# FPGA_PART2.net
KiCad netlist of a schematic drawn in Altium Designer
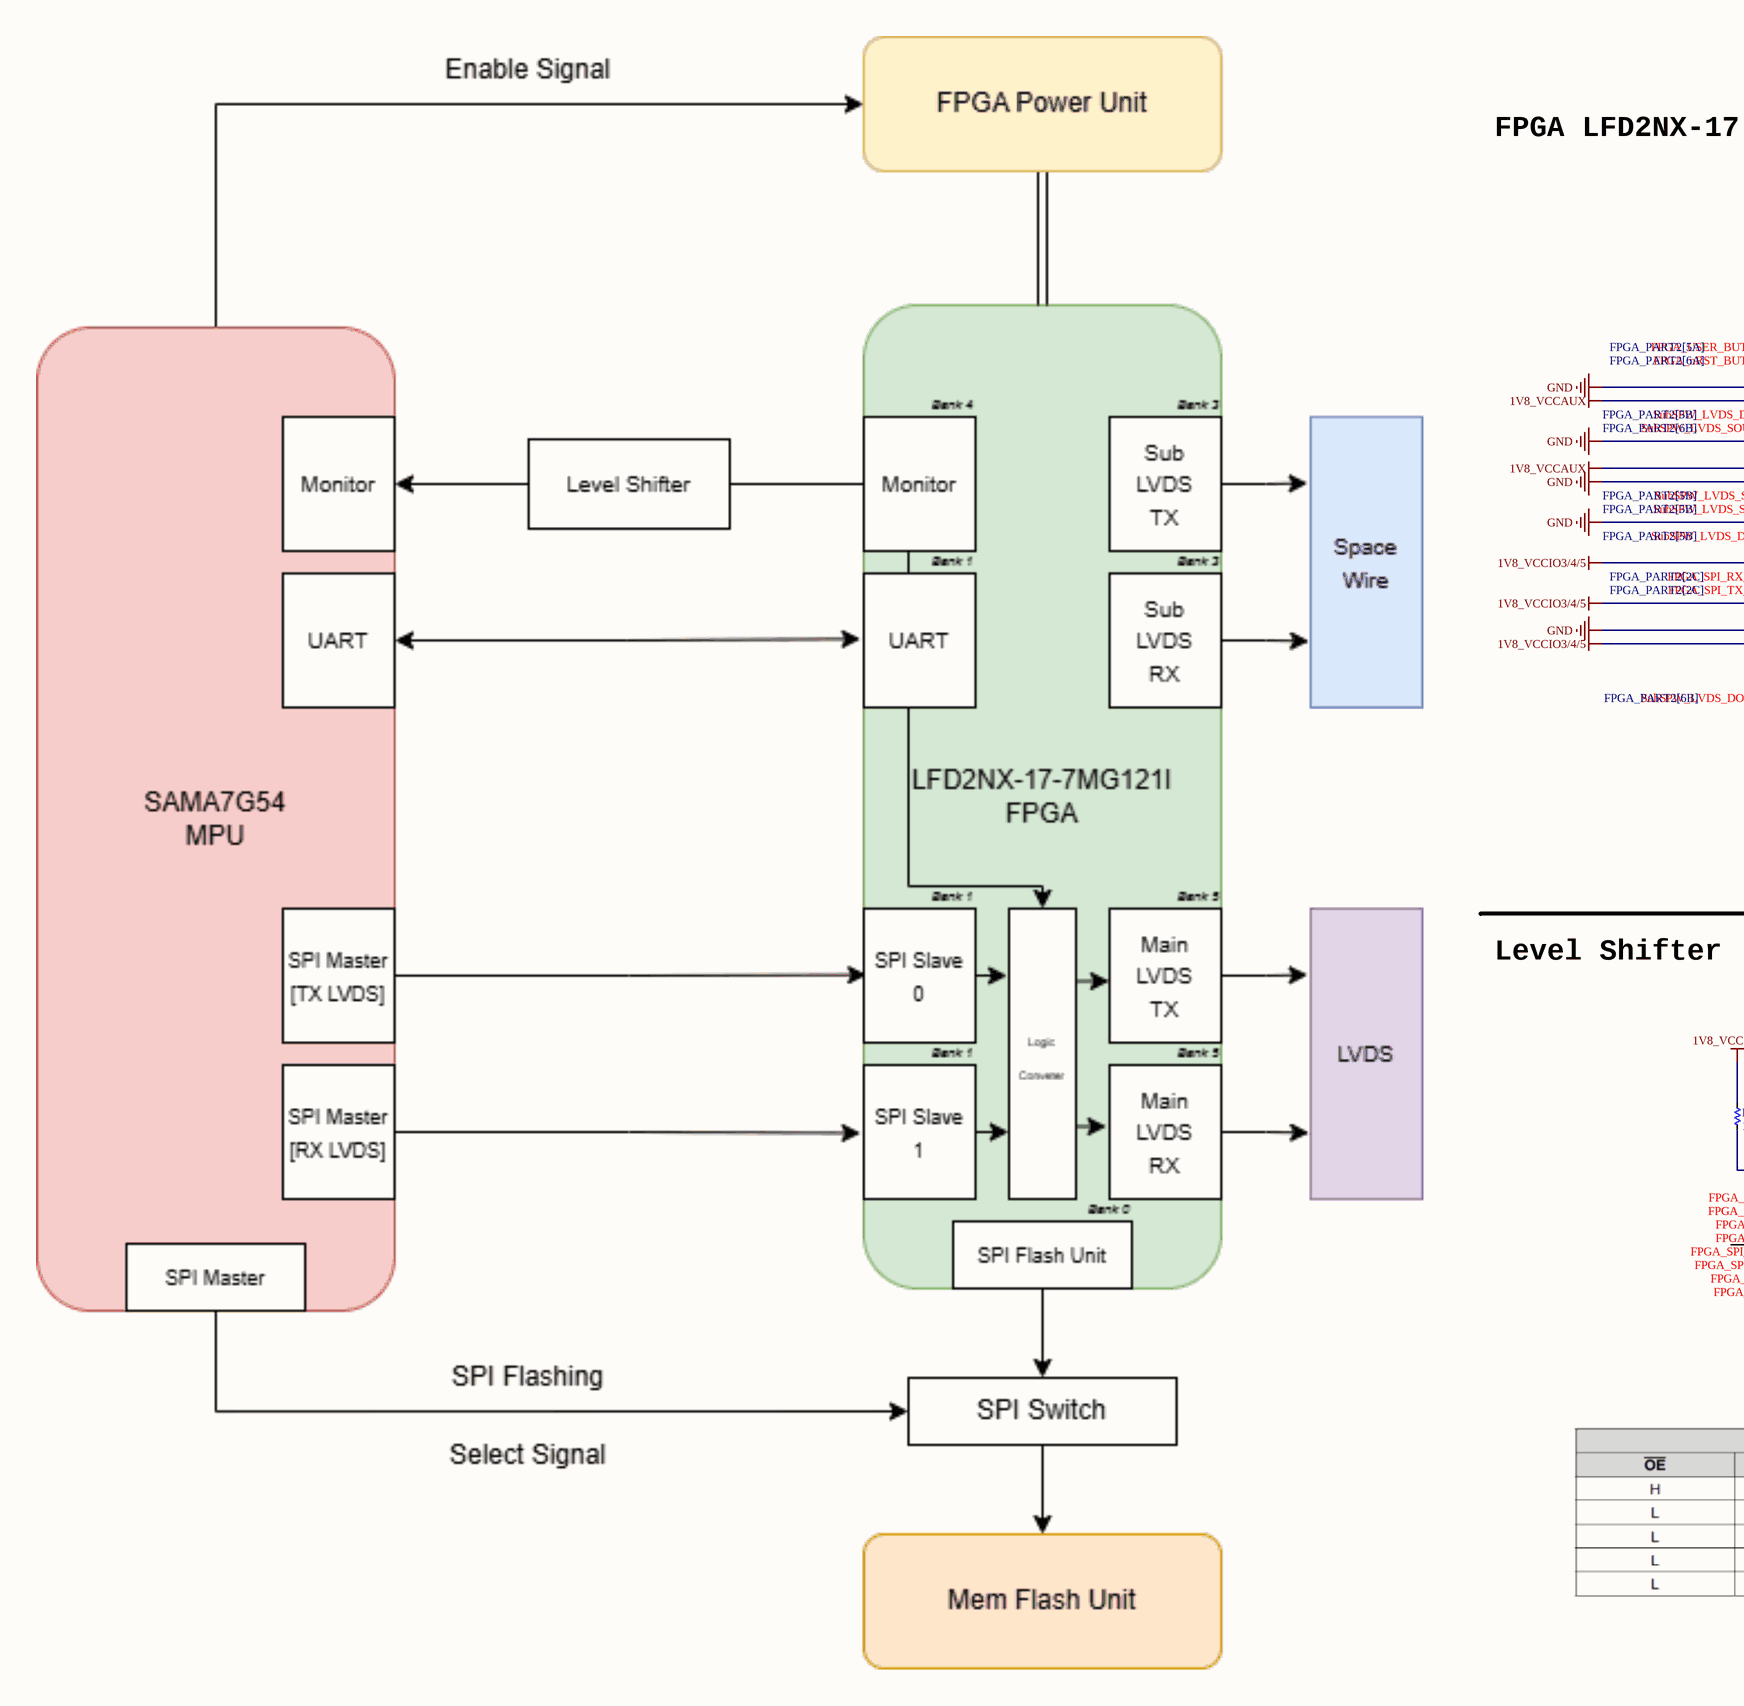
[diagram p0: FPGA_PART2.SchDoc, left]
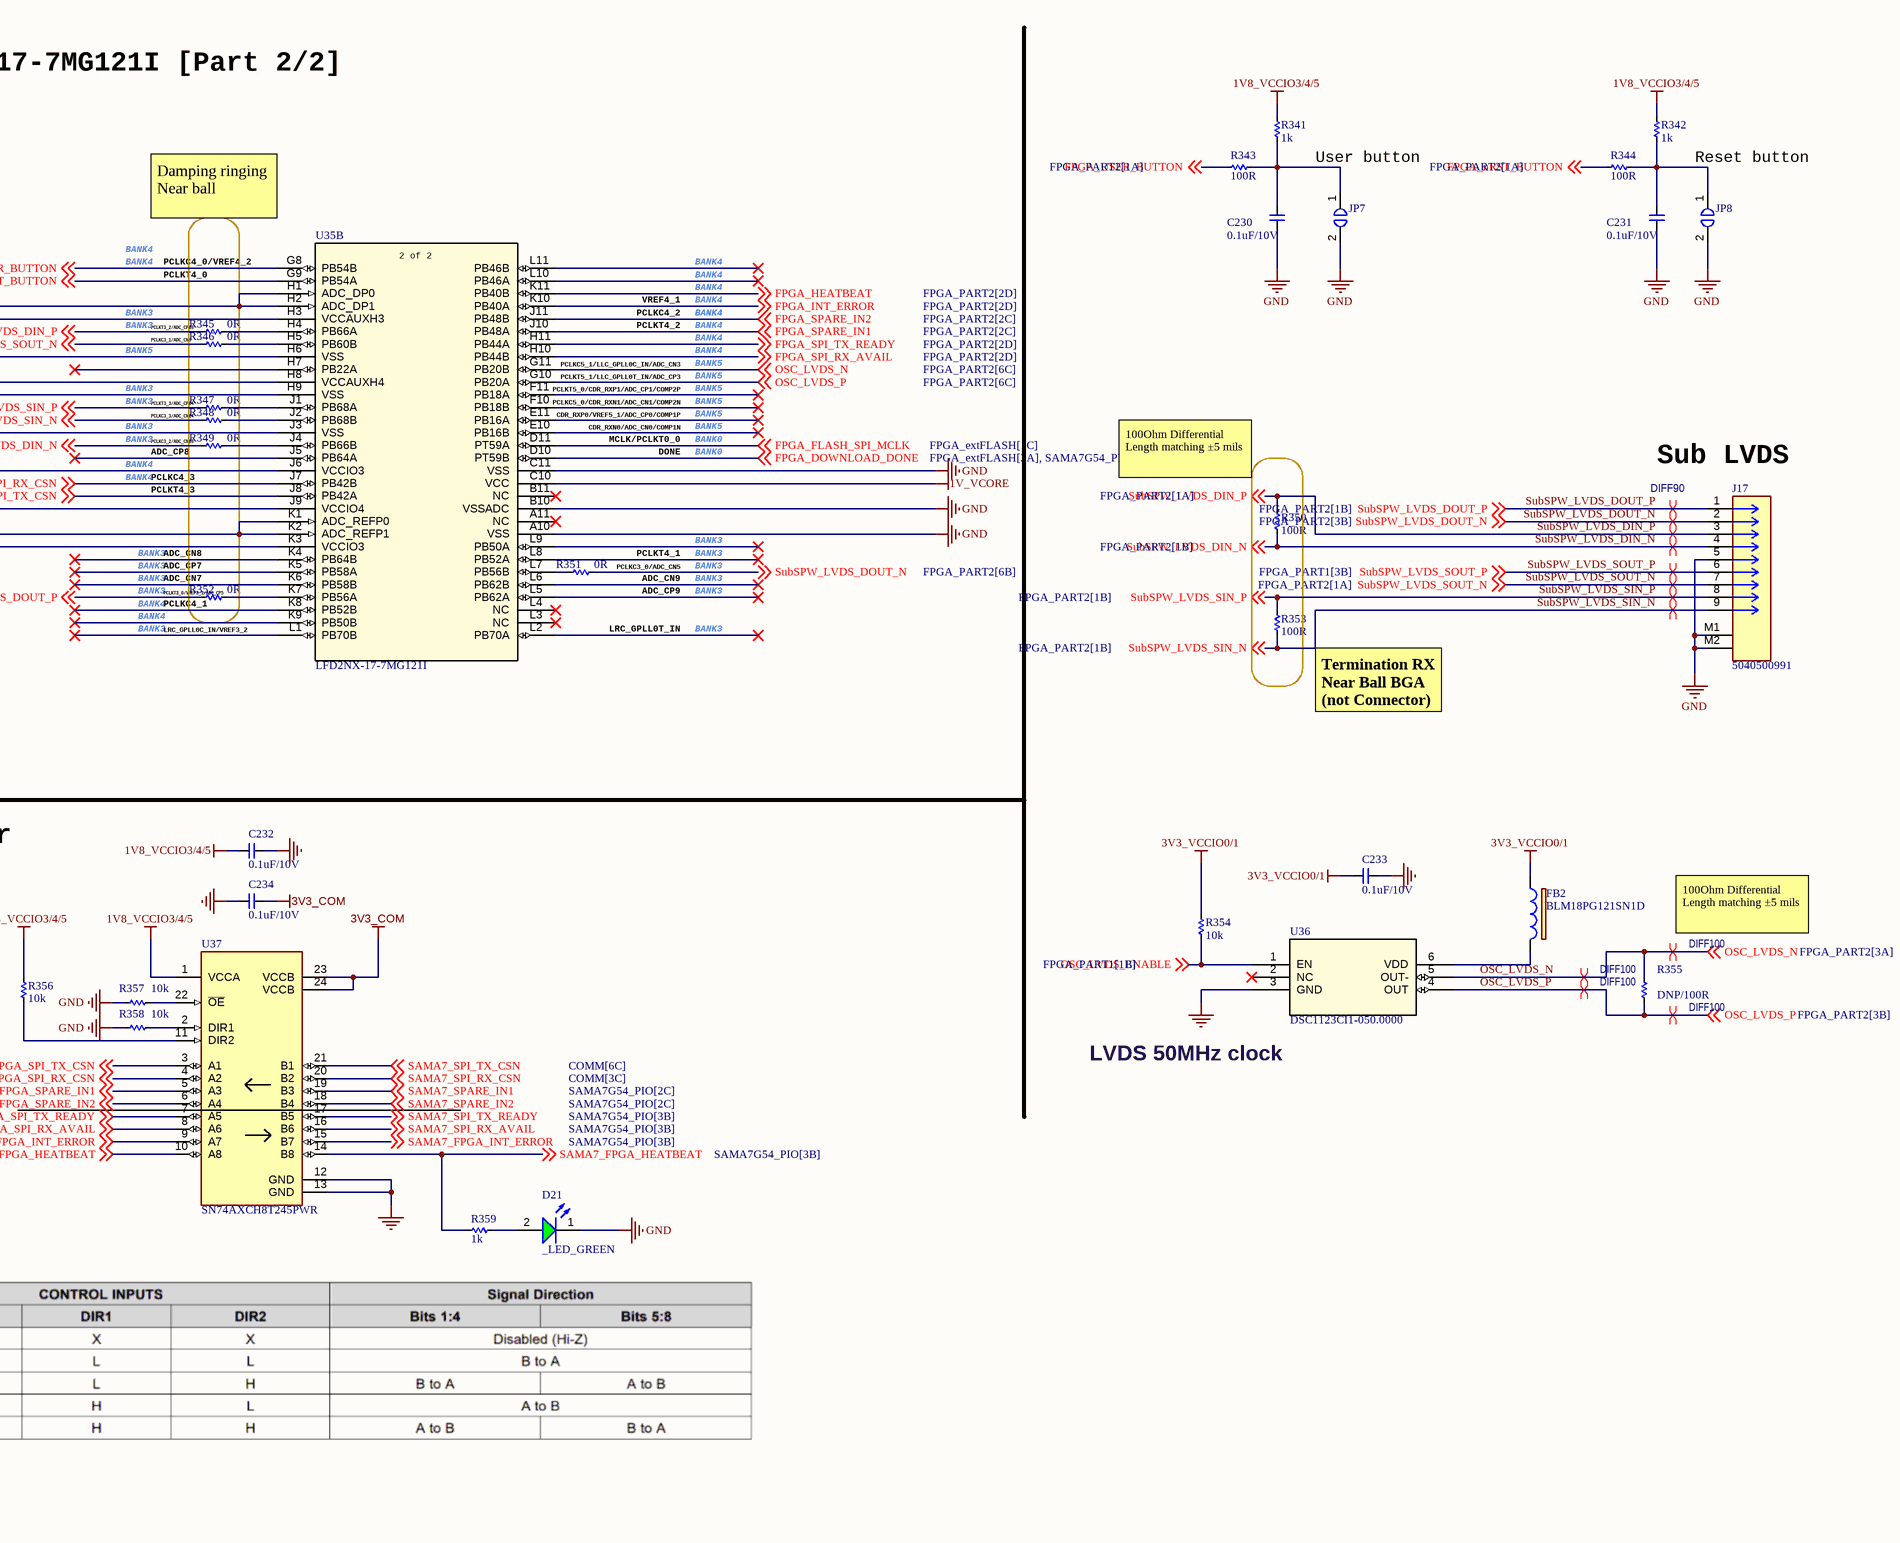
[diagram p1: FPGA_PART2.SchDoc, right]

(export (version "E")
  (design (tool "Eeschema 10.0.6"))
  (components
    (comp (ref "C230")
      (value "0.1uF/10V")
      (footprint "CAP_C_1005X50_L")
      (description "CAP")
      (libsource (lib "LABLIB") (part "_CAP_C_2"))
    )
    (comp (ref "C231")
      (value "0.1uF/10V")
      (footprint "CAP_C_1005X50_L")
      (description "CAP")
      (libsource (lib "LABLIB") (part "_CAP_C_2"))
    )
    (comp (ref "C232")
      (value "0.1uF/10V")
      (footprint "CAP_C_1005X50_L")
      (description "CAP")
      (libsource (lib "LABLIB") (part "_CAP_C_2"))
    )
    (comp (ref "C233")
      (value "0.1uF/10V")
      (footprint "CAP_C_1005X50_L")
      (description "CAP")
      (libsource (lib "LABLIB") (part "_CAP_C_2"))
    )
    (comp (ref "C234")
      (value "0.1uF/10V")
      (footprint "CAP_C_1005X50_L")
      (description "CAP")
      (libsource (lib "LABLIB") (part "_CAP_C_2"))
    )
    (comp (ref "D21")
      (value "_LED_GREEN")
      (footprint "LED_0603")
      (description "LED GREEN CLEAR 0603 SMD")
      (libsource (lib "IFBschelib") (part "LED_GREEN"))
    )
    (comp (ref "FB2")
      (value "BLM18PG121SN1D")
      (footprint "IND_C_1608X60")
      (description "FERRITE BEAD 120 OHM 0603 1LN")
      (fields (field (name "COPYRIGHT") "Copyright (C) 2025 Ultra Librarian. All rights reserved."))
      (libsource (lib "IFBschelib") (part "BLM18PG121SN1D"))
    )
    (comp (ref "J17")
      (value "5040500991")
      (footprint "MOLEX_5040500991")
      (description "Connector Header Surface Mount, Right Angle 9 position 0.059\" (1.50mm)")
      (libsource (lib "IFBschelib") (part "5040500991"))
    )
    (comp (ref "JP7") (value "~") (footprint "JUMPER_1608") (libsource (lib "LABLIB") (part "JUMPER_1_1")))
    (comp (ref "JP8") (value "~") (footprint "JUMPER_1608") (libsource (lib "LABLIB") (part "JUMPER_1_1")))
    (comp (ref "R341")
      (value "1k")
      (footprint "RES_C_1005x30_L")
      (description "RES")
      (libsource (lib "LABLIB") (part "_RES_B_2"))
    )
    (comp (ref "R342")
      (value "1k")
      (footprint "RES_C_1005x30_L")
      (description "RES")
      (libsource (lib "LABLIB") (part "_RES_B_2"))
    )
    (comp (ref "R343")
      (value "100R")
      (footprint "RES_C_1005x30_L")
      (description "RES")
      (libsource (lib "LABLIB") (part "_RES_B_2"))
    )
    (comp (ref "R344")
      (value "100R")
      (footprint "RES_C_1005x30_L")
      (description "RES")
      (libsource (lib "LABLIB") (part "_RES_B_2"))
    )
    (comp (ref "R345")
      (value "0R")
      (footprint "RES_C_1005x30_L")
      (description "RES")
      (libsource (lib "LABLIB") (part "_RES_B_2"))
    )
    (comp (ref "R346")
      (value "0R")
      (footprint "RES_C_1005x30_L")
      (description "RES")
      (libsource (lib "LABLIB") (part "_RES_B_2"))
    )
    (comp (ref "R347")
      (value "0R")
      (footprint "RES_C_1005x30_L")
      (description "RES")
      (libsource (lib "LABLIB") (part "_RES_B_2"))
    )
    (comp (ref "R348")
      (value "0R")
      (footprint "RES_C_1005x30_L")
      (description "RES")
      (libsource (lib "LABLIB") (part "_RES_B_2"))
    )
    (comp (ref "R349")
      (value "0R")
      (footprint "RES_C_1005x30_L")
      (description "RES")
      (libsource (lib "LABLIB") (part "_RES_B_2"))
    )
    (comp (ref "R350")
      (value "100R")
      (footprint "RES_C_1005x30_L")
      (description "RES")
      (libsource (lib "LABLIB") (part "_RES_B_2"))
    )
    (comp (ref "R351")
      (value "0R")
      (footprint "RES_C_1005x30_L")
      (description "RES")
      (libsource (lib "LABLIB") (part "_RES_B_2"))
    )
    (comp (ref "R352")
      (value "0R")
      (footprint "RES_C_1005x30_L")
      (description "RES")
      (libsource (lib "LABLIB") (part "_RES_B_2"))
    )
    (comp (ref "R353")
      (value "100R")
      (footprint "RES_C_1005x30_L")
      (description "RES")
      (libsource (lib "LABLIB") (part "_RES_B_2"))
    )
    (comp (ref "R354")
      (value "10k")
      (footprint "RES_C_1005x30_L")
      (description "RES")
      (libsource (lib "LABLIB") (part "_RES_B_2"))
    )
    (comp (ref "R355")
      (value "DNP/100R")
      (footprint "RES_C_1005x30_L")
      (description "RES")
      (libsource (lib "IFBschelib") (part "_RES_B_2"))
    )
    (comp (ref "R356")
      (value "10k")
      (footprint "RES_C_1005x30_L")
      (description "RES")
      (libsource (lib "LABLIB") (part "_RES_B_2"))
    )
    (comp (ref "R357")
      (value "10k")
      (footprint "RES_C_1005x30_L")
      (description "RES")
      (libsource (lib "LABLIB") (part "_RES_B_2"))
    )
    (comp (ref "R358")
      (value "10k")
      (footprint "RES_C_1005x30_L")
      (description "RES")
      (libsource (lib "LABLIB") (part "_RES_B_2"))
    )
    (comp (ref "R359")
      (value "1k")
      (footprint "RES_C_1005x30_L")
      (description "RES")
      (libsource (lib "LABLIB") (part "_RES_B_2"))
    )
    (comp (ref "U35")
      (value "LFD2NX-17-7MG121I")
      (footprint "csfBGA121_LAT")
      (description "Description")
      (fields (field (name "COPYRIGHT") "Copyright (C) 2025 Ultra Librarian. All rights reserved."))
      (libsource (lib "IFBschelib_offline") (part "LFD2NX-17-7MG121I"))
    )
    (comp (ref "U36")
      (value "DSC1123CI1-050.0000")
      (footprint "VDFN6_3P2X2P5_MCH")
      (description "No Description Available")
      (fields
        (field (name "MANUFACTURER_PART_NUMBER") "DSC1103CI2-180.0000T")
        (field (name "COPYRIGHT") "Copyright (C) 2026 Ultra Librarian. All rights reserved.")
      )
      (libsource (lib "IFBschelib") (part "DSC11x3CIx-x"))
    )
    (comp (ref "U37")
      (value "SN74AXCH8T245PWR")
      (footprint "SOP65P640X120-24N")
      (description "8-Bit Dual-Supply Bus Transceiver")
      (fields (field (name "MF") "Texas Instruments"))
      (libsource (lib "LABLIB") (part "IC_voltage_level_SN74AXCH8T245PWR"))
    )
  )
  (nets
    (net (code "1") (name "1V8_VCCAUX") (class "Default")
      (node (ref "U35") (pin "H3") (pinfunction "VCCAUXH3_H3") (pintype "power_in"))
      (node (ref "U35") (pin "H8") (pinfunction "VCCAUXH4_H8") (pintype "power_in"))
    )
    (net (code "2") (name "1V8_VCCIO3{slash}4{slash}5") (class "Default")
      (node (ref "C232") (pin "2") (pinfunction "2_2") (pintype "passive"))
      (node (ref "R341") (pin "2") (pinfunction "2_2") (pintype "passive"))
      (node (ref "R342") (pin "2") (pinfunction "2_2") (pintype "passive"))
      (node (ref "R356") (pin "2") (pinfunction "2_2") (pintype "passive"))
      (node (ref "U35") (pin "J6") (pinfunction "VCCIO3_J6") (pintype "power_in"))
      (node (ref "U35") (pin "J9") (pinfunction "VCCIO4_J9") (pintype "power_in"))
      (node (ref "U35") (pin "K3") (pinfunction "VCCIO3_K3") (pintype "power_in"))
      (node (ref "U37") (pin "1") (pinfunction "VCCA_1") (pintype "power_in"))
    )
    (net (code "3") (name "1V_VCORE") (class "Default")
      (node (ref "U35") (pin "C10") (pinfunction "VCC_C10") (pintype "power_in"))
    )
    (net (code "4") (name "3V3_COM") (class "Default")
      (node (ref "C234") (pin "2") (pinfunction "2_2") (pintype "passive"))
      (node (ref "U37") (pin "23") (pinfunction "VCCB_23") (pintype "power_in"))
      (node (ref "U37") (pin "24") (pinfunction "VCCB_24") (pintype "power_in"))
    )
    (net (code "5") (name "3V3_VCCIO0{slash}1") (class "Default")
      (node (ref "C233") (pin "2") (pinfunction "2_2") (pintype "passive"))
      (node (ref "FB2") (pin "2") (pinfunction "2_2") (pintype "passive"))
      (node (ref "R354") (pin "2") (pinfunction "2_2") (pintype "passive"))
    )
    (net (code "6") (name "FPGA_DOWNLOAD_DONE") (class "Default")
      (node (ref "U35") (pin "D10") (pinfunction "PT59B_D10") (pintype "bidirectional"))
    )
    (net (code "7") (name "FPGA_FLASH_SPI_MCLK") (class "Default")
      (node (ref "U35") (pin "D11") (pinfunction "PT59A_D11") (pintype "bidirectional"))
    )
    (net (code "8") (name "FPGA_HEATBEAT") (class "Default")
      (node (ref "U35") (pin "K11") (pinfunction "PB40B_K11") (pintype "bidirectional"))
      (node (ref "U37") (pin "10") (pinfunction "A8_10") (pintype "bidirectional"))
    )
    (net (code "9") (name "FPGA_INT_ERROR") (class "Default")
      (node (ref "U35") (pin "K10") (pinfunction "PB40A_K10") (pintype "bidirectional"))
      (node (ref "U37") (pin "9") (pinfunction "A7_9") (pintype "bidirectional"))
    )
    (net (code "10") (name "FPGA_SPARE_IN1") (class "Default")
      (node (ref "U35") (pin "J10") (pinfunction "PB48A_J10") (pintype "bidirectional"))
      (node (ref "U37") (pin "5") (pinfunction "A3_5") (pintype "bidirectional"))
    )
    (net (code "11") (name "FPGA_SPARE_IN2") (class "Default")
      (node (ref "U35") (pin "J11") (pinfunction "PB48B_J11") (pintype "bidirectional"))
      (node (ref "U37") (pin "6") (pinfunction "A4_6") (pintype "bidirectional"))
    )
    (net (code "12") (name "FPGA_SPI_RX_AVAIL") (class "Default")
      (node (ref "U35") (pin "H10") (pinfunction "PB44B_H10") (pintype "bidirectional"))
      (node (ref "U37") (pin "8") (pinfunction "A6_8") (pintype "bidirectional"))
    )
    (net (code "13") (name "FPGA_SPI_RX_CSN") (class "Default")
      (node (ref "U35") (pin "J7") (pinfunction "PB42B_J7") (pintype "bidirectional"))
      (node (ref "U37") (pin "4") (pinfunction "A2_4") (pintype "bidirectional"))
    )
    (net (code "14") (name "FPGA_SPI_TX_CSN") (class "Default")
      (node (ref "U35") (pin "J8") (pinfunction "PB42A_J8") (pintype "bidirectional"))
      (node (ref "U37") (pin "3") (pinfunction "A1_3") (pintype "bidirectional"))
    )
    (net (code "15") (name "FPGA_SPI_TX_READY") (class "Default")
      (node (ref "U35") (pin "H11") (pinfunction "PB44A_H11") (pintype "bidirectional"))
      (node (ref "U37") (pin "7") (pinfunction "A5_7") (pintype "bidirectional"))
    )
    (net (code "16") (name "FPGA_USER_BUTTON") (class "Default")
      (node (ref "R343") (pin "1") (pinfunction "1_1") (pintype "passive"))
      (node (ref "U35") (pin "G8") (pinfunction "PB54B_G8") (pintype "bidirectional"))
    )
    (net (code "17") (name "FPGA_nRST_BUTTON") (class "Default")
      (node (ref "R344") (pin "1") (pinfunction "1_1") (pintype "passive"))
      (node (ref "U35") (pin "G9") (pinfunction "PB54A_G9") (pintype "bidirectional"))
    )
    (net (code "18") (name "GND") (class "Default")
      (node (ref "C230") (pin "1") (pinfunction "1_1") (pintype "passive"))
      (node (ref "C231") (pin "1") (pinfunction "1_1") (pintype "passive"))
      (node (ref "C232") (pin "1") (pinfunction "1_1") (pintype "passive"))
      (node (ref "C233") (pin "1") (pinfunction "1_1") (pintype "passive"))
      (node (ref "C234") (pin "1") (pinfunction "1_1") (pintype "passive"))
      (node (ref "D21") (pin "1") (pinfunction "K_1") (pintype "passive"))
      (node (ref "J17") (pin "5") (pinfunction "5_5") (pintype "passive"))
      (node (ref "J17") (pin "M1") (pinfunction "M1_M1") (pintype "passive"))
      (node (ref "J17") (pin "M2") (pinfunction "M2_M2") (pintype "passive"))
      (node (ref "JP7") (pin "2") (pinfunction "2_2") (pintype "passive"))
      (node (ref "JP8") (pin "2") (pinfunction "2_2") (pintype "passive"))
      (node (ref "R357") (pin "1") (pinfunction "1_1") (pintype "passive"))
      (node (ref "R358") (pin "1") (pinfunction "1_1") (pintype "passive"))
      (node (ref "U35") (pin "A10") (pinfunction "VSS_A10") (pintype "power_in"))
      (node (ref "U35") (pin "B10") (pinfunction "VSSADC_B10") (pintype "power_in"))
      (node (ref "U35") (pin "C11") (pinfunction "VSS_C11") (pintype "power_in"))
      (node (ref "U35") (pin "H1") (pinfunction "ADC_DP0_H1") (pintype "input"))
      (node (ref "U35") (pin "H2") (pinfunction "ADC_DP1_H2") (pintype "input"))
      (node (ref "U35") (pin "H6") (pinfunction "VSS_H6") (pintype "power_in"))
      (node (ref "U35") (pin "H9") (pinfunction "VSS_H9") (pintype "power_in"))
      (node (ref "U35") (pin "J3") (pinfunction "VSS_J3") (pintype "power_in"))
      (node (ref "U35") (pin "K1") (pinfunction "ADC_REFP0_K1") (pintype "input"))
      (node (ref "U35") (pin "K2") (pinfunction "ADC_REFP1_K2") (pintype "input"))
      (node (ref "U36") (pin "3") (pinfunction "GND_3") (pintype "power_in"))
      (node (ref "U37") (pin "12") (pinfunction "GND_12") (pintype "power_in"))
      (node (ref "U37") (pin "13") (pinfunction "GND_13") (pintype "power_in"))
    )
    (net (code "19") (name "Net-(C230-Pad2)") (class "Default")
      (node (ref "C230") (pin "2") (pinfunction "2_2") (pintype "passive"))
      (node (ref "JP7") (pin "1") (pinfunction "1_1") (pintype "passive"))
      (node (ref "R341") (pin "1") (pinfunction "1_1") (pintype "passive"))
      (node (ref "R343") (pin "2") (pinfunction "2_2") (pintype "passive"))
    )
    (net (code "20") (name "Net-(C231-Pad2)") (class "Default")
      (node (ref "C231") (pin "2") (pinfunction "2_2") (pintype "passive"))
      (node (ref "JP8") (pin "1") (pinfunction "1_1") (pintype "passive"))
      (node (ref "R342") (pin "1") (pinfunction "1_1") (pintype "passive"))
      (node (ref "R344") (pin "2") (pinfunction "2_2") (pintype "passive"))
    )
    (net (code "21") (name "Net-(D21-A)") (class "Default")
      (node (ref "D21") (pin "2") (pinfunction "A_2") (pintype "passive"))
      (node (ref "R359") (pin "1") (pinfunction "1_1") (pintype "passive"))
    )
    (net (code "22") (name "Net-(U35B-PB56A)") (class "Default")
      (node (ref "R352") (pin "1") (pinfunction "1_1") (pintype "passive"))
      (node (ref "U35") (pin "K7") (pinfunction "PB56A_K7") (pintype "bidirectional"))
    )
    (net (code "23") (name "Net-(U35B-PB56B)") (class "Default")
      (node (ref "R351") (pin "2") (pinfunction "2_2") (pintype "passive"))
      (node (ref "U35") (pin "L7") (pinfunction "PB56B_L7") (pintype "bidirectional"))
    )
    (net (code "24") (name "Net-(U35B-PB60B)") (class "Default")
      (node (ref "R346") (pin "1") (pinfunction "1_1") (pintype "passive"))
      (node (ref "U35") (pin "H5") (pinfunction "PB60B_H5") (pintype "bidirectional"))
    )
    (net (code "25") (name "Net-(U35B-PB66A)") (class "Default")
      (node (ref "R345") (pin "1") (pinfunction "1_1") (pintype "passive"))
      (node (ref "U35") (pin "H4") (pinfunction "PB66A_H4") (pintype "bidirectional"))
    )
    (net (code "26") (name "Net-(U35B-PB66B)") (class "Default")
      (node (ref "R349") (pin "1") (pinfunction "1_1") (pintype "passive"))
      (node (ref "U35") (pin "J4") (pinfunction "PB66B_J4") (pintype "bidirectional"))
    )
    (net (code "27") (name "Net-(U35B-PB68A)") (class "Default")
      (node (ref "R347") (pin "1") (pinfunction "1_1") (pintype "passive"))
      (node (ref "U35") (pin "J1") (pinfunction "PB68A_J1") (pintype "bidirectional"))
    )
    (net (code "28") (name "Net-(U35B-PB68B)") (class "Default")
      (node (ref "R348") (pin "1") (pinfunction "1_1") (pintype "passive"))
      (node (ref "U35") (pin "J2") (pinfunction "PB68B_J2") (pintype "bidirectional"))
    )
    (net (code "29") (name "Net-(U36-VDD)") (class "Default")
      (node (ref "FB2") (pin "1") (pinfunction "1_1") (pintype "passive"))
      (node (ref "U36") (pin "6") (pinfunction "VDD_6") (pintype "power_in"))
    )
    (net (code "30") (name "Net-(U37-DIR1)") (class "Default")
      (node (ref "R358") (pin "2") (pinfunction "2_2") (pintype "passive"))
      (node (ref "U37") (pin "2") (pinfunction "DIR1_2") (pintype "input"))
    )
    (net (code "31") (name "Net-(U37-DIR2)") (class "Default")
      (node (ref "R356") (pin "1") (pinfunction "1_1") (pintype "passive"))
      (node (ref "U37") (pin "11") (pinfunction "DIR2_11") (pintype "input"))
    )
    (net (code "32") (name "Net-(U37-~{OE})") (class "Default")
      (node (ref "R357") (pin "2") (pinfunction "2_2") (pintype "passive"))
      (node (ref "U37") (pin "22") (pinfunction "~{OE}_22") (pintype "input"))
    )
    (net (code "33") (name "OSC_LVDS_ENABLE") (class "Default")
      (node (ref "R354") (pin "1") (pinfunction "1_1") (pintype "passive"))
      (node (ref "U36") (pin "1") (pinfunction "EN_1") (pintype "passive"))
    )
    (net (code "34") (name "OSC_LVDS_N") (class "Default")
      (node (ref "R355") (pin "1") (pinfunction "1_1") (pintype "passive"))
      (node (ref "U35") (pin "G11") (pinfunction "PB20B_G11") (pintype "bidirectional"))
      (node (ref "U36") (pin "5") (pinfunction "OUT-_5") (pintype "bidirectional"))
    )
    (net (code "35") (name "OSC_LVDS_P") (class "Default")
      (node (ref "R355") (pin "2") (pinfunction "2_2") (pintype "passive"))
      (node (ref "U35") (pin "G10") (pinfunction "PB20A_G10") (pintype "bidirectional"))
      (node (ref "U36") (pin "4") (pinfunction "OUT_4") (pintype "bidirectional"))
    )
    (net (code "36") (name "SAMA7_FPGA_HEATBEAT") (class "Default")
      (node (ref "R359") (pin "2") (pinfunction "2_2") (pintype "passive"))
      (node (ref "U37") (pin "14") (pinfunction "B8_14") (pintype "bidirectional"))
    )
    (net (code "37") (name "SAMA7_FPGA_INT_ERROR") (class "Default")
      (node (ref "U37") (pin "15") (pinfunction "B7_15") (pintype "bidirectional"))
    )
    (net (code "38") (name "SAMA7_SPARE_IN1") (class "Default")
      (node (ref "U37") (pin "19") (pinfunction "B3_19") (pintype "bidirectional"))
    )
    (net (code "39") (name "SAMA7_SPARE_IN2") (class "Default")
      (node (ref "U37") (pin "18") (pinfunction "B4_18") (pintype "bidirectional"))
    )
    (net (code "40") (name "SAMA7_SPI_RX_AVAIL") (class "Default")
      (node (ref "U37") (pin "16") (pinfunction "B6_16") (pintype "bidirectional"))
    )
    (net (code "41") (name "SAMA7_SPI_RX_CSN") (class "Default")
      (node (ref "U37") (pin "20") (pinfunction "B2_20") (pintype "bidirectional"))
    )
    (net (code "42") (name "SAMA7_SPI_TX_CSN") (class "Default")
      (node (ref "U37") (pin "21") (pinfunction "B1_21") (pintype "bidirectional"))
    )
    (net (code "43") (name "SAMA7_SPI_TX_READY") (class "Default")
      (node (ref "U37") (pin "17") (pinfunction "B5_17") (pintype "bidirectional"))
    )
    (net (code "44") (name "SubSPW_LVDS_DIN_N") (class "Default")
      (node (ref "J17") (pin "4") (pinfunction "4_4") (pintype "passive"))
      (node (ref "R349") (pin "2") (pinfunction "2_2") (pintype "passive"))
      (node (ref "R350") (pin "2") (pinfunction "2_2") (pintype "passive"))
    )
    (net (code "45") (name "SubSPW_LVDS_DIN_P") (class "Default")
      (node (ref "J17") (pin "3") (pinfunction "3_3") (pintype "passive"))
      (node (ref "R345") (pin "2") (pinfunction "2_2") (pintype "passive"))
      (node (ref "R350") (pin "1") (pinfunction "1_1") (pintype "passive"))
    )
    (net (code "46") (name "SubSPW_LVDS_DOUT_N") (class "Default")
      (node (ref "J17") (pin "2") (pinfunction "2_2") (pintype "passive"))
      (node (ref "R351") (pin "1") (pinfunction "1_1") (pintype "passive"))
    )
    (net (code "47") (name "SubSPW_LVDS_DOUT_P") (class "Default")
      (node (ref "J17") (pin "1") (pinfunction "1_1") (pintype "passive"))
      (node (ref "R352") (pin "2") (pinfunction "2_2") (pintype "passive"))
    )
    (net (code "48") (name "SubSPW_LVDS_SIN_N") (class "Default")
      (node (ref "J17") (pin "9") (pinfunction "9_9") (pintype "passive"))
      (node (ref "R348") (pin "2") (pinfunction "2_2") (pintype "passive"))
      (node (ref "R353") (pin "2") (pinfunction "2_2") (pintype "passive"))
    )
    (net (code "49") (name "SubSPW_LVDS_SIN_P") (class "Default")
      (node (ref "J17") (pin "8") (pinfunction "8_8") (pintype "passive"))
      (node (ref "R347") (pin "2") (pinfunction "2_2") (pintype "passive"))
      (node (ref "R353") (pin "1") (pinfunction "1_1") (pintype "passive"))
    )
    (net (code "50") (name "SubSPW_LVDS_SOUT_N") (class "Default")
      (node (ref "J17") (pin "7") (pinfunction "7_7") (pintype "passive"))
      (node (ref "R346") (pin "2") (pinfunction "2_2") (pintype "passive"))
    )
    (net (code "51") (name "SubSPW_LVDS_SOUT_P") (class "Default")
      (node (ref "J17") (pin "6") (pinfunction "6_6") (pintype "passive"))
    )
    (net (code "52") (name "unconnected-(U35B-NC-PadA11)") (class "Default")
      (node (ref "U35") (pin "A11") (pinfunction "NC_A11") (pintype "passive+no_connect"))
    )
    (net (code "53") (name "unconnected-(U35B-NC-PadB11)") (class "Default")
      (node (ref "U35") (pin "B11") (pinfunction "NC_B11") (pintype "passive+no_connect"))
    )
    (net (code "54") (name "unconnected-(U35B-NC-PadL3)") (class "Default")
      (node (ref "U35") (pin "L3") (pinfunction "NC_L3") (pintype "passive+no_connect"))
    )
    (net (code "55") (name "unconnected-(U35B-NC-PadL4)") (class "Default")
      (node (ref "U35") (pin "L4") (pinfunction "NC_L4") (pintype "passive+no_connect"))
    )
    (net (code "56") (name "unconnected-(U35B-PB16A-PadE11)") (class "Default")
      (node (ref "U35") (pin "E11") (pinfunction "PB16A_E11") (pintype "bidirectional+no_connect"))
    )
    (net (code "57") (name "unconnected-(U35B-PB16B-PadE10)") (class "Default")
      (node (ref "U35") (pin "E10") (pinfunction "PB16B_E10") (pintype "bidirectional+no_connect"))
    )
    (net (code "58") (name "unconnected-(U35B-PB18A-PadF11)") (class "Default")
      (node (ref "U35") (pin "F11") (pinfunction "PB18A_F11") (pintype "bidirectional+no_connect"))
    )
    (net (code "59") (name "unconnected-(U35B-PB18B-PadF10)") (class "Default")
      (node (ref "U35") (pin "F10") (pinfunction "PB18B_F10") (pintype "bidirectional+no_connect"))
    )
    (net (code "60") (name "unconnected-(U35B-PB22A-PadH7)") (class "Default")
      (node (ref "U35") (pin "H7") (pinfunction "PB22A_H7") (pintype "bidirectional+no_connect"))
    )
    (net (code "61") (name "unconnected-(U35B-PB46A-PadL10)") (class "Default")
      (node (ref "U35") (pin "L10") (pinfunction "PB46A_L10") (pintype "bidirectional+no_connect"))
    )
    (net (code "62") (name "unconnected-(U35B-PB46B-PadL11)") (class "Default")
      (node (ref "U35") (pin "L11") (pinfunction "PB46B_L11") (pintype "bidirectional+no_connect"))
    )
    (net (code "63") (name "unconnected-(U35B-PB50A-PadL9)") (class "Default")
      (node (ref "U35") (pin "L9") (pinfunction "PB50A_L9") (pintype "bidirectional+no_connect"))
    )
    (net (code "64") (name "unconnected-(U35B-PB50B-PadK9)") (class "Default")
      (node (ref "U35") (pin "K9") (pinfunction "PB50B_K9") (pintype "bidirectional+no_connect"))
    )
    (net (code "65") (name "unconnected-(U35B-PB52A-PadL8)") (class "Default")
      (node (ref "U35") (pin "L8") (pinfunction "PB52A_L8") (pintype "bidirectional+no_connect"))
    )
    (net (code "66") (name "unconnected-(U35B-PB52B-PadK8)") (class "Default")
      (node (ref "U35") (pin "K8") (pinfunction "PB52B_K8") (pintype "bidirectional+no_connect"))
    )
    (net (code "67") (name "unconnected-(U35B-PB58A-PadK5)") (class "Default")
      (node (ref "U35") (pin "K5") (pinfunction "PB58A_K5") (pintype "bidirectional+no_connect"))
    )
    (net (code "68") (name "unconnected-(U35B-PB58B-PadK6)") (class "Default")
      (node (ref "U35") (pin "K6") (pinfunction "PB58B_K6") (pintype "bidirectional+no_connect"))
    )
    (net (code "69") (name "unconnected-(U35B-PB62A-PadL5)") (class "Default")
      (node (ref "U35") (pin "L5") (pinfunction "PB62A_L5") (pintype "bidirectional+no_connect"))
    )
    (net (code "70") (name "unconnected-(U35B-PB62B-PadL6)") (class "Default")
      (node (ref "U35") (pin "L6") (pinfunction "PB62B_L6") (pintype "bidirectional+no_connect"))
    )
    (net (code "71") (name "unconnected-(U35B-PB64A-PadJ5)") (class "Default")
      (node (ref "U35") (pin "J5") (pinfunction "PB64A_J5") (pintype "bidirectional+no_connect"))
    )
    (net (code "72") (name "unconnected-(U35B-PB64B-PadK4)") (class "Default")
      (node (ref "U35") (pin "K4") (pinfunction "PB64B_K4") (pintype "bidirectional+no_connect"))
    )
    (net (code "73") (name "unconnected-(U35B-PB70A-PadL2)") (class "Default")
      (node (ref "U35") (pin "L2") (pinfunction "PB70A_L2") (pintype "bidirectional+no_connect"))
    )
    (net (code "74") (name "unconnected-(U35B-PB70B-PadL1)") (class "Default")
      (node (ref "U35") (pin "L1") (pinfunction "PB70B_L1") (pintype "bidirectional+no_connect"))
    )
    (net (code "75") (name "unconnected-(U36-NC-Pad2)") (class "Default")
      (node (ref "U36") (pin "2") (pinfunction "NC_2") (pintype "passive+no_connect"))
    )
  )
)
